# Sheet1.net
KiCad netlist of a schematic drawn in Altium Designer
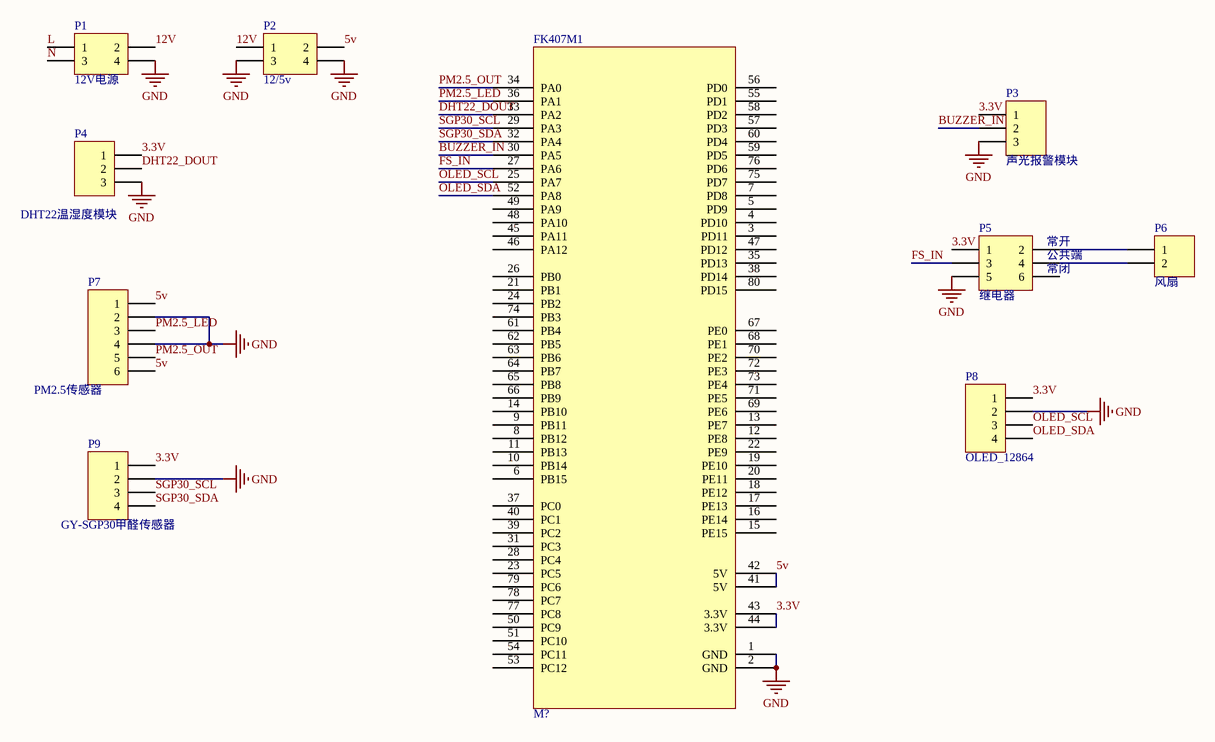
[diagram p0: Sheet1.SchDoc]

(export (version "E")
  (design (tool "Eeschema 10.0.6"))
  (components
    (comp (ref "FK407M1") (value "M?") (footprint "FK407M1") (libsource (lib "核心板元件库") (part "FK407M1")))
    (comp (ref "P1")
      (value "12V电源")
      (footprint "HDR2X2")
      (description "Header, 2-Pin, Dual row")
      (fields (field (name "PUBLISHER") "Altium Limited"))
      (libsource (lib "Miscellaneous Connectors") (part "Header 2X2"))
    )
    (comp (ref "P2")
      (value "12/5v")
      (footprint "HDR2X2")
      (description "Header, 2-Pin, Dual row")
      (fields (field (name "PUBLISHER") "Altium Limited"))
      (libsource (lib "Miscellaneous Connectors") (part "Header 2X2"))
    )
    (comp (ref "P3")
      (value "声光报警模块")
      (footprint "HDR1X3")
      (description "Header, 3-Pin")
      (fields (field (name "PUBLISHER") "Altium Limited"))
      (libsource (lib "") (part "Header 3_1"))
    )
    (comp (ref "P4")
      (value "DHT22温湿度模块")
      (footprint "HDR1X3")
      (description "Header, 3-Pin")
      (fields (field (name "PUBLISHER") "Altium Limited"))
      (libsource (lib "Miscellaneous Connectors") (part "Header 3"))
    )
    (comp (ref "P5")
      (value "继电器")
      (footprint "HDR2X3")
      (description "Header, 3-Pin, Dual row")
      (fields (field (name "PUBLISHER") "Altium Limited"))
      (libsource (lib "Miscellaneous Connectors") (part "Header 3X2"))
    )
    (comp (ref "P6")
      (value "风扇")
      (footprint "HDR1X2")
      (description "Header, 2-Pin")
      (fields (field (name "PUBLISHER") "Altium Limited"))
      (libsource (lib "Miscellaneous Connectors") (part "Header 2"))
    )
    (comp (ref "P7")
      (value "PM2.5传感器")
      (footprint "HDR1X6")
      (description "Header, 6-Pin")
      (fields (field (name "PUBLISHER") "Altium Limited"))
      (libsource (lib "Miscellaneous Connectors") (part "Header 6"))
    )
    (comp (ref "P8")
      (value "OLED_12864")
      (footprint "HDR1X4")
      (description "Header, 4-Pin")
      (fields (field (name "PUBLISHER") "Altium Limited"))
      (libsource (lib "Miscellaneous Connectors") (part "Header 4"))
    )
    (comp (ref "P9")
      (value "GY-SGP30甲醛传感器")
      (footprint "HDR1X4")
      (description "Header, 4-Pin")
      (fields (field (name "PUBLISHER") "Altium Limited"))
      (libsource (lib "Miscellaneous Connectors") (part "Header 4"))
    )
  )
  (nets
    (net (code "1") (name "/3.3V") (class "Default")
      (node (ref "FK407M1") (pin "43") (pinfunction "3.3V_43") (pintype "passive"))
      (node (ref "FK407M1") (pin "44") (pinfunction "3.3V_44") (pintype "passive"))
      (node (ref "P3") (pin "1") (pinfunction "1_1") (pintype "passive"))
      (node (ref "P4") (pin "1") (pinfunction "1_1") (pintype "passive"))
      (node (ref "P5") (pin "1") (pinfunction "1_1") (pintype "passive"))
      (node (ref "P8") (pin "1") (pinfunction "1_1") (pintype "passive"))
      (node (ref "P9") (pin "1") (pinfunction "1_1") (pintype "passive"))
    )
    (net (code "2") (name "/5v") (class "Default")
      (node (ref "FK407M1") (pin "41") (pinfunction "5V_41") (pintype "passive"))
      (node (ref "FK407M1") (pin "42") (pinfunction "5V_42") (pintype "passive"))
      (node (ref "P2") (pin "2") (pinfunction "2_2") (pintype "passive"))
      (node (ref "P7") (pin "1") (pinfunction "1_1") (pintype "passive"))
      (node (ref "P7") (pin "6") (pinfunction "6_6") (pintype "passive"))
    )
    (net (code "3") (name "/12V") (class "Default")
      (node (ref "P1") (pin "2") (pinfunction "2_2") (pintype "passive"))
      (node (ref "P2") (pin "1") (pinfunction "1_1") (pintype "passive"))
    )
    (net (code "4") (name "/BUZZER_IN") (class "Default")
      (node (ref "FK407M1") (pin "30") (pinfunction "PA5_30") (pintype "passive"))
      (node (ref "P3") (pin "2") (pinfunction "2_2") (pintype "passive"))
    )
    (net (code "5") (name "/DHT22_DOUT") (class "Default")
      (node (ref "FK407M1") (pin "33") (pinfunction "PA2_33") (pintype "passive"))
      (node (ref "P4") (pin "2") (pinfunction "2_2") (pintype "passive"))
    )
    (net (code "6") (name "/FS_IN") (class "Default")
      (node (ref "FK407M1") (pin "27") (pinfunction "PA6_27") (pintype "passive"))
      (node (ref "P5") (pin "3") (pinfunction "3_3") (pintype "passive"))
    )
    (net (code "7") (name "/L") (class "Default")
      (node (ref "P1") (pin "1") (pinfunction "1_1") (pintype "passive"))
    )
    (net (code "8") (name "/N") (class "Default")
      (node (ref "P1") (pin "3") (pinfunction "3_3") (pintype "passive"))
    )
    (net (code "9") (name "/OLED_SCL") (class "Default")
      (node (ref "FK407M1") (pin "25") (pinfunction "PA7_25") (pintype "passive"))
      (node (ref "P8") (pin "3") (pinfunction "3_3") (pintype "passive"))
    )
    (net (code "10") (name "/OLED_SDA") (class "Default")
      (node (ref "FK407M1") (pin "52") (pinfunction "PA8_52") (pintype "passive"))
      (node (ref "P8") (pin "4") (pinfunction "4_4") (pintype "passive"))
    )
    (net (code "11") (name "/PM2.5_LED") (class "Default")
      (node (ref "FK407M1") (pin "36") (pinfunction "PA1_36") (pintype "passive"))
      (node (ref "P7") (pin "3") (pinfunction "3_3") (pintype "passive"))
    )
    (net (code "12") (name "/PM2.5_OUT") (class "Default")
      (node (ref "FK407M1") (pin "34") (pinfunction "PA0_34") (pintype "passive"))
      (node (ref "P7") (pin "5") (pinfunction "5_5") (pintype "passive"))
    )
    (net (code "13") (name "/SGP30_SCL") (class "Default")
      (node (ref "FK407M1") (pin "29") (pinfunction "PA3_29") (pintype "passive"))
      (node (ref "P9") (pin "3") (pinfunction "3_3") (pintype "passive"))
    )
    (net (code "14") (name "/SGP30_SDA") (class "Default")
      (node (ref "FK407M1") (pin "32") (pinfunction "PA4_32") (pintype "passive"))
      (node (ref "P9") (pin "4") (pinfunction "4_4") (pintype "passive"))
    )
    (net (code "15") (name "GND") (class "Default")
      (node (ref "FK407M1") (pin "1") (pinfunction "GND_1") (pintype "passive"))
      (node (ref "FK407M1") (pin "2") (pinfunction "GND_2") (pintype "passive"))
      (node (ref "P1") (pin "4") (pinfunction "4_4") (pintype "passive"))
      (node (ref "P2") (pin "3") (pinfunction "3_3") (pintype "passive"))
      (node (ref "P2") (pin "4") (pinfunction "4_4") (pintype "passive"))
      (node (ref "P3") (pin "3") (pinfunction "3_3") (pintype "passive"))
      (node (ref "P4") (pin "3") (pinfunction "3_3") (pintype "passive"))
      (node (ref "P5") (pin "5") (pinfunction "5_5") (pintype "passive"))
      (node (ref "P7") (pin "2") (pinfunction "2_2") (pintype "passive"))
      (node (ref "P7") (pin "4") (pinfunction "4_4") (pintype "passive"))
      (node (ref "P8") (pin "2") (pinfunction "2_2") (pintype "passive"))
      (node (ref "P9") (pin "2") (pinfunction "2_2") (pintype "passive"))
    )
    (net (code "16") (name "Net-(P5-Pad2)") (class "Default")
      (node (ref "P5") (pin "2") (pinfunction "2_2") (pintype "passive"))
      (node (ref "P6") (pin "1") (pinfunction "1_1") (pintype "passive"))
    )
    (net (code "17") (name "Net-(P5-Pad4)") (class "Default")
      (node (ref "P5") (pin "4") (pinfunction "4_4") (pintype "passive"))
      (node (ref "P6") (pin "2") (pinfunction "2_2") (pintype "passive"))
    )
    (net (code "18") (name "unconnected-(FK407M1-PA9-Pad49)") (class "Default")
      (node (ref "FK407M1") (pin "49") (pinfunction "PA9_49") (pintype "passive"))
    )
    (net (code "19") (name "unconnected-(FK407M1-PA10-Pad48)") (class "Default")
      (node (ref "FK407M1") (pin "48") (pinfunction "PA10_48") (pintype "passive"))
    )
    (net (code "20") (name "unconnected-(FK407M1-PA11-Pad45)") (class "Default")
      (node (ref "FK407M1") (pin "45") (pinfunction "PA11_45") (pintype "passive"))
    )
    (net (code "21") (name "unconnected-(FK407M1-PA12-Pad46)") (class "Default")
      (node (ref "FK407M1") (pin "46") (pinfunction "PA12_46") (pintype "passive"))
    )
    (net (code "22") (name "unconnected-(FK407M1-PB0-Pad26)") (class "Default")
      (node (ref "FK407M1") (pin "26") (pinfunction "PB0_26") (pintype "passive"))
    )
    (net (code "23") (name "unconnected-(FK407M1-PB1-Pad21)") (class "Default")
      (node (ref "FK407M1") (pin "21") (pinfunction "PB1_21") (pintype "passive"))
    )
    (net (code "24") (name "unconnected-(FK407M1-PB2-Pad24)") (class "Default")
      (node (ref "FK407M1") (pin "24") (pinfunction "PB2_24") (pintype "passive"))
    )
    (net (code "25") (name "unconnected-(FK407M1-PB3-Pad74)") (class "Default")
      (node (ref "FK407M1") (pin "74") (pinfunction "PB3_74") (pintype "passive"))
    )
    (net (code "26") (name "unconnected-(FK407M1-PB4-Pad61)") (class "Default")
      (node (ref "FK407M1") (pin "61") (pinfunction "PB4_61") (pintype "passive"))
    )
    (net (code "27") (name "unconnected-(FK407M1-PB5-Pad62)") (class "Default")
      (node (ref "FK407M1") (pin "62") (pinfunction "PB5_62") (pintype "passive"))
    )
    (net (code "28") (name "unconnected-(FK407M1-PB6-Pad63)") (class "Default")
      (node (ref "FK407M1") (pin "63") (pinfunction "PB6_63") (pintype "passive"))
    )
    (net (code "29") (name "unconnected-(FK407M1-PB7-Pad64)") (class "Default")
      (node (ref "FK407M1") (pin "64") (pinfunction "PB7_64") (pintype "passive"))
    )
    (net (code "30") (name "unconnected-(FK407M1-PB8-Pad65)") (class "Default")
      (node (ref "FK407M1") (pin "65") (pinfunction "PB8_65") (pintype "passive"))
    )
    (net (code "31") (name "unconnected-(FK407M1-PB9-Pad66)") (class "Default")
      (node (ref "FK407M1") (pin "66") (pinfunction "PB9_66") (pintype "passive"))
    )
    (net (code "32") (name "unconnected-(FK407M1-PB10-Pad14)") (class "Default")
      (node (ref "FK407M1") (pin "14") (pinfunction "PB10_14") (pintype "passive"))
    )
    (net (code "33") (name "unconnected-(FK407M1-PB11-Pad9)") (class "Default")
      (node (ref "FK407M1") (pin "9") (pinfunction "PB11_9") (pintype "passive"))
    )
    (net (code "34") (name "unconnected-(FK407M1-PB12-Pad8)") (class "Default")
      (node (ref "FK407M1") (pin "8") (pinfunction "PB12_8") (pintype "passive"))
    )
    (net (code "35") (name "unconnected-(FK407M1-PB13-Pad11)") (class "Default")
      (node (ref "FK407M1") (pin "11") (pinfunction "PB13_11") (pintype "passive"))
    )
    (net (code "36") (name "unconnected-(FK407M1-PB14-Pad10)") (class "Default")
      (node (ref "FK407M1") (pin "10") (pinfunction "PB14_10") (pintype "passive"))
    )
    (net (code "37") (name "unconnected-(FK407M1-PB15-Pad6)") (class "Default")
      (node (ref "FK407M1") (pin "6") (pinfunction "PB15_6") (pintype "passive"))
    )
    (net (code "38") (name "unconnected-(FK407M1-PC0-Pad37)") (class "Default")
      (node (ref "FK407M1") (pin "37") (pinfunction "PC0_37") (pintype "passive"))
    )
    (net (code "39") (name "unconnected-(FK407M1-PC1-Pad40)") (class "Default")
      (node (ref "FK407M1") (pin "40") (pinfunction "PC1_40") (pintype "passive"))
    )
    (net (code "40") (name "unconnected-(FK407M1-PC2-Pad39)") (class "Default")
      (node (ref "FK407M1") (pin "39") (pinfunction "PC2_39") (pintype "passive"))
    )
    (net (code "41") (name "unconnected-(FK407M1-PC3-Pad31)") (class "Default")
      (node (ref "FK407M1") (pin "31") (pinfunction "PC3_31") (pintype "passive"))
    )
    (net (code "42") (name "unconnected-(FK407M1-PC4-Pad28)") (class "Default")
      (node (ref "FK407M1") (pin "28") (pinfunction "PC4_28") (pintype "passive"))
    )
    (net (code "43") (name "unconnected-(FK407M1-PC5-Pad23)") (class "Default")
      (node (ref "FK407M1") (pin "23") (pinfunction "PC5_23") (pintype "passive"))
    )
    (net (code "44") (name "unconnected-(FK407M1-PC6-Pad79)") (class "Default")
      (node (ref "FK407M1") (pin "79") (pinfunction "PC6_79") (pintype "passive"))
    )
    (net (code "45") (name "unconnected-(FK407M1-PC7-Pad78)") (class "Default")
      (node (ref "FK407M1") (pin "78") (pinfunction "PC7_78") (pintype "passive"))
    )
    (net (code "46") (name "unconnected-(FK407M1-PC8-Pad77)") (class "Default")
      (node (ref "FK407M1") (pin "77") (pinfunction "PC8_77") (pintype "passive"))
    )
    (net (code "47") (name "unconnected-(FK407M1-PC9-Pad50)") (class "Default")
      (node (ref "FK407M1") (pin "50") (pinfunction "PC9_50") (pintype "passive"))
    )
    (net (code "48") (name "unconnected-(FK407M1-PC10-Pad51)") (class "Default")
      (node (ref "FK407M1") (pin "51") (pinfunction "PC10_51") (pintype "passive"))
    )
    (net (code "49") (name "unconnected-(FK407M1-PC11-Pad54)") (class "Default")
      (node (ref "FK407M1") (pin "54") (pinfunction "PC11_54") (pintype "passive"))
    )
    (net (code "50") (name "unconnected-(FK407M1-PC12-Pad53)") (class "Default")
      (node (ref "FK407M1") (pin "53") (pinfunction "PC12_53") (pintype "passive"))
    )
    (net (code "51") (name "unconnected-(FK407M1-PD0-Pad56)") (class "Default")
      (node (ref "FK407M1") (pin "56") (pinfunction "PD0_56") (pintype "passive"))
    )
    (net (code "52") (name "unconnected-(FK407M1-PD1-Pad55)") (class "Default")
      (node (ref "FK407M1") (pin "55") (pinfunction "PD1_55") (pintype "passive"))
    )
    (net (code "53") (name "unconnected-(FK407M1-PD2-Pad58)") (class "Default")
      (node (ref "FK407M1") (pin "58") (pinfunction "PD2_58") (pintype "passive"))
    )
    (net (code "54") (name "unconnected-(FK407M1-PD3-Pad57)") (class "Default")
      (node (ref "FK407M1") (pin "57") (pinfunction "PD3_57") (pintype "passive"))
    )
    (net (code "55") (name "unconnected-(FK407M1-PD4-Pad60)") (class "Default")
      (node (ref "FK407M1") (pin "60") (pinfunction "PD4_60") (pintype "passive"))
    )
    (net (code "56") (name "unconnected-(FK407M1-PD5-Pad59)") (class "Default")
      (node (ref "FK407M1") (pin "59") (pinfunction "PD5_59") (pintype "passive"))
    )
    (net (code "57") (name "unconnected-(FK407M1-PD6-Pad76)") (class "Default")
      (node (ref "FK407M1") (pin "76") (pinfunction "PD6_76") (pintype "passive"))
    )
    (net (code "58") (name "unconnected-(FK407M1-PD7-Pad75)") (class "Default")
      (node (ref "FK407M1") (pin "75") (pinfunction "PD7_75") (pintype "passive"))
    )
    (net (code "59") (name "unconnected-(FK407M1-PD8-Pad7)") (class "Default")
      (node (ref "FK407M1") (pin "7") (pinfunction "PD8_7") (pintype "passive"))
    )
    (net (code "60") (name "unconnected-(FK407M1-PD9-Pad5)") (class "Default")
      (node (ref "FK407M1") (pin "5") (pinfunction "PD9_5") (pintype "passive"))
    )
    (net (code "61") (name "unconnected-(FK407M1-PD10-Pad4)") (class "Default")
      (node (ref "FK407M1") (pin "4") (pinfunction "PD10_4") (pintype "passive"))
    )
    (net (code "62") (name "unconnected-(FK407M1-PD11-Pad3)") (class "Default")
      (node (ref "FK407M1") (pin "3") (pinfunction "PD11_3") (pintype "passive"))
    )
    (net (code "63") (name "unconnected-(FK407M1-PD12-Pad47)") (class "Default")
      (node (ref "FK407M1") (pin "47") (pinfunction "PD12_47") (pintype "passive"))
    )
    (net (code "64") (name "unconnected-(FK407M1-PD13-Pad35)") (class "Default")
      (node (ref "FK407M1") (pin "35") (pinfunction "PD13_35") (pintype "passive"))
    )
    (net (code "65") (name "unconnected-(FK407M1-PD14-Pad38)") (class "Default")
      (node (ref "FK407M1") (pin "38") (pinfunction "PD14_38") (pintype "passive"))
    )
    (net (code "66") (name "unconnected-(FK407M1-PD15-Pad80)") (class "Default")
      (node (ref "FK407M1") (pin "80") (pinfunction "PD15_80") (pintype "passive"))
    )
    (net (code "67") (name "unconnected-(FK407M1-PE0-Pad67)") (class "Default")
      (node (ref "FK407M1") (pin "67") (pinfunction "PE0_67") (pintype "passive"))
    )
    (net (code "68") (name "unconnected-(FK407M1-PE1-Pad68)") (class "Default")
      (node (ref "FK407M1") (pin "68") (pinfunction "PE1_68") (pintype "passive"))
    )
    (net (code "69") (name "unconnected-(FK407M1-PE2-Pad70)") (class "Default")
      (node (ref "FK407M1") (pin "70") (pinfunction "PE2_70") (pintype "passive"))
    )
    (net (code "70") (name "unconnected-(FK407M1-PE3-Pad72)") (class "Default")
      (node (ref "FK407M1") (pin "72") (pinfunction "PE3_72") (pintype "passive"))
    )
    (net (code "71") (name "unconnected-(FK407M1-PE4-Pad73)") (class "Default")
      (node (ref "FK407M1") (pin "73") (pinfunction "PE4_73") (pintype "passive"))
    )
    (net (code "72") (name "unconnected-(FK407M1-PE5-Pad71)") (class "Default")
      (node (ref "FK407M1") (pin "71") (pinfunction "PE5_71") (pintype "passive"))
    )
    (net (code "73") (name "unconnected-(FK407M1-PE6-Pad69)") (class "Default")
      (node (ref "FK407M1") (pin "69") (pinfunction "PE6_69") (pintype "passive"))
    )
    (net (code "74") (name "unconnected-(FK407M1-PE7-Pad13)") (class "Default")
      (node (ref "FK407M1") (pin "13") (pinfunction "PE7_13") (pintype "passive"))
    )
    (net (code "75") (name "unconnected-(FK407M1-PE8-Pad12)") (class "Default")
      (node (ref "FK407M1") (pin "12") (pinfunction "PE8_12") (pintype "passive"))
    )
    (net (code "76") (name "unconnected-(FK407M1-PE9-Pad22)") (class "Default")
      (node (ref "FK407M1") (pin "22") (pinfunction "PE9_22") (pintype "passive"))
    )
    (net (code "77") (name "unconnected-(FK407M1-PE10-Pad19)") (class "Default")
      (node (ref "FK407M1") (pin "19") (pinfunction "PE10_19") (pintype "passive"))
    )
    (net (code "78") (name "unconnected-(FK407M1-PE11-Pad20)") (class "Default")
      (node (ref "FK407M1") (pin "20") (pinfunction "PE11_20") (pintype "passive"))
    )
    (net (code "79") (name "unconnected-(FK407M1-PE12-Pad18)") (class "Default")
      (node (ref "FK407M1") (pin "18") (pinfunction "PE12_18") (pintype "passive"))
    )
    (net (code "80") (name "unconnected-(FK407M1-PE13-Pad17)") (class "Default")
      (node (ref "FK407M1") (pin "17") (pinfunction "PE13_17") (pintype "passive"))
    )
    (net (code "81") (name "unconnected-(FK407M1-PE14-Pad16)") (class "Default")
      (node (ref "FK407M1") (pin "16") (pinfunction "PE14_16") (pintype "passive"))
    )
    (net (code "82") (name "unconnected-(FK407M1-PE15-Pad15)") (class "Default")
      (node (ref "FK407M1") (pin "15") (pinfunction "PE15_15") (pintype "passive"))
    )
    (net (code "83") (name "unconnected-(P5-Pad6)") (class "Default")
      (node (ref "P5") (pin "6") (pinfunction "6_6") (pintype "passive"))
    )
  )
)
